# schema.net
KiCad netlist of a schematic drawn in EasyEDA
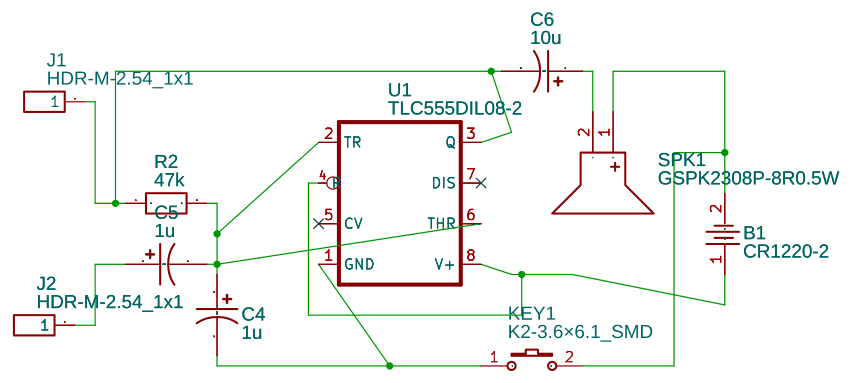
[diagram p0: schematic sheet]

(export (version "E")
  (design (tool "Eeschema 10.0.6"))
  (components
    (comp (ref "B1")
      (value "CR1220-2")
      (fields (field (name "Manufacturer") "Q&J"))
      (libsource (lib "") (part "CR1220-2"))
    )
    (comp (ref "C4") (value "1u") (libsource (lib "") (part "C_Tan_SMD_A_US")))
    (comp (ref "C5") (value "1u") (libsource (lib "") (part "C_Tan_SMD_A_US_2")))
    (comp (ref "C6") (value "10u") (libsource (lib "") (part "C_Tan_SMD_A_US_1")))
    (comp (ref "J1") (value "HDR-M-2.54_1x1") (libsource (lib "") (part "HDR-M-2.54_1x1")))
    (comp (ref "J2") (value "HDR-M-2.54_1x1") (libsource (lib "") (part "HDR-M-2.54_1x1")))
    (comp (ref "KEY1")
      (value "K2-3.6×6.1_SMD")
      (fields (field (name "Manufacturer Part") "K2-1107ST-A4SW-06"))
      (libsource (lib "") (part "K2-3.6×6.1_SMD"))
    )
    (comp (ref "R2") (value "47k") (libsource (lib "") (part "R_0603_EU")))
    (comp (ref "SPK1")
      (value "GSPK2308P-8R0.5W")
      (fields (field (name "Manufacturer") "INGHAi(赢海)"))
      (libsource (lib "") (part "GSPK2308P-8R0.5W"))
    )
    (comp (ref "U1") (value "TLC555DIL08-2") (libsource (lib "") (part "TLC555DIL08-2")))
  )
  (nets
    (net (code "1") (name "Net-(C5-Pad1)") (class "Default")
      (node (ref "C5") (pin "1") (pinfunction "1_1") (pintype "unspecified"))
      (node (ref "J2") (pin "1") (pinfunction "1_1") (pintype "input"))
    )
    (net (code "2") (name "Net-(SPK1-+)") (class "Default")
      (node (ref "B1") (pin "2") (pinfunction "2_2") (pintype "input"))
      (node (ref "KEY1") (pin "2") (pinfunction "2_2") (pintype "unspecified"))
      (node (ref "SPK1") (pin "1") (pinfunction "+_1") (pintype "unspecified"))
    )
    (net (code "3") (name "Net-(SPK1--)") (class "Default")
      (node (ref "C6") (pin "1") (pinfunction "1_1") (pintype "unspecified"))
      (node (ref "SPK1") (pin "2") (pinfunction "-_2") (pintype "unspecified"))
    )
    (net (code "4") (name "Net-(U1-GND)") (class "Default")
      (node (ref "C4") (pin "2") (pinfunction "2_2") (pintype "unspecified"))
      (node (ref "KEY1") (pin "1") (pinfunction "1_1") (pintype "unspecified"))
      (node (ref "U1") (pin "1") (pinfunction "GND_1") (pintype "passive"))
    )
    (net (code "5") (name "Net-(U1-Q)") (class "Default")
      (node (ref "C6") (pin "2") (pinfunction "2_2") (pintype "unspecified"))
      (node (ref "J1") (pin "1") (pinfunction "1_1") (pintype "input"))
      (node (ref "R2") (pin "1") (pinfunction "1_1") (pintype "unspecified"))
      (node (ref "U1") (pin "3") (pinfunction "Q_3") (pintype "output"))
    )
    (net (code "6") (name "Net-(U1-R)") (class "Default")
      (node (ref "B1") (pin "1") (pinfunction "1_1") (pintype "input"))
      (node (ref "U1") (pin "4") (pinfunction "R_4") (pintype "input"))
      (node (ref "U1") (pin "8") (pinfunction "V+_8") (pintype "passive"))
    )
    (net (code "7") (name "Net-(U1-THR)") (class "Default")
      (node (ref "C4") (pin "1") (pinfunction "1_1") (pintype "unspecified"))
      (node (ref "C5") (pin "2") (pinfunction "2_2") (pintype "unspecified"))
      (node (ref "R2") (pin "2") (pinfunction "2_2") (pintype "unspecified"))
      (node (ref "U1") (pin "2") (pinfunction "TR_2") (pintype "input"))
      (node (ref "U1") (pin "6") (pinfunction "THR_6") (pintype "input"))
    )
    (net (code "8") (name "unconnected-(U1-CV-Pad5)") (class "Default")
      (node (ref "U1") (pin "5") (pinfunction "CV_5") (pintype "input+no_connect"))
    )
    (net (code "9") (name "unconnected-(U1-DIS-Pad7)") (class "Default")
      (node (ref "U1") (pin "7") (pinfunction "DIS_7") (pintype "input+no_connect"))
    )
  )
)
